# SensWear_DaughterBoard.net
KiCad netlist of a schematic drawn in Altium Designer
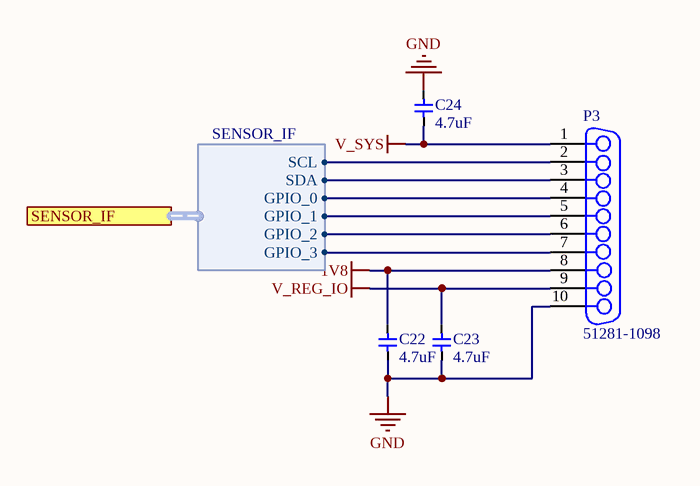
[diagram p0: SensWear_DaughterBoard.SchDoc]

(export (version "E")
  (design (tool "Eeschema 10.0.6"))
  (components
    (comp (ref "C22")
      (value "4.7uF")
      (footprint "CAPC1005X05N")
      (description "Multilayer Ceramic Capacitor, 4.7 uF, 10 V, ± 20%, X5R, 0402 [1005 Metric]")
      (fields
        (field (name "MANUFACTURER") "Murata")
        (field (name "MANUFACTURER PART NUMBER") "GRM155R61A475MEAAD")
      )
      (libsource (lib "OpenRingComponents") (part "GRM155R61A475MEAAD"))
    )
    (comp (ref "C23")
      (value "4.7uF")
      (footprint "CAPC1005X05N")
      (description "Multilayer Ceramic Capacitor, 4.7 uF, 10 V, ± 20%, X5R, 0402 [1005 Metric]")
      (fields
        (field (name "MANUFACTURER") "Murata")
        (field (name "MANUFACTURER PART NUMBER") "GRM155R61A475MEAAD")
      )
      (libsource (lib "OpenRingComponents") (part "GRM155R61A475MEAAD"))
    )
    (comp (ref "C24")
      (value "4.7uF")
      (footprint "CAPC1005X05N")
      (description "Multilayer Ceramic Capacitor, 4.7 uF, 10 V, ± 20%, X5R, 0402 [1005 Metric]")
      (fields
        (field (name "MANUFACTURER") "Murata")
        (field (name "MANUFACTURER PART NUMBER") "GRM155R61A475MEAAD")
      )
      (libsource (lib "OpenRingComponents") (part "GRM155R61A475MEAAD"))
    )
    (comp (ref "P3")
      (value "51281-1098")
      (footprint "51281-1098")
      (description "FFC/FPC Connector, Surface Mount, Right-Angle, Non-ZIF, Dual Contact Style")
      (fields (field (name "MANUFACTURER") "Molex"))
      (libsource (lib "Connectors") (part "51281-1098"))
    )
  )
  (nets
    (net (code "2") (name "/GPIO_0") (class "Default")
      (node (ref "P3") (pin "4") (pinfunction "4_4") (pintype "passive"))
    )
    (net (code "3") (name "/GPIO_1") (class "Default")
      (node (ref "P3") (pin "5") (pinfunction "5_5") (pintype "passive"))
    )
    (net (code "4") (name "/GPIO_2") (class "Default")
      (node (ref "P3") (pin "6") (pinfunction "6_6") (pintype "passive"))
    )
    (net (code "5") (name "/GPIO_3") (class "Default")
      (node (ref "P3") (pin "7") (pinfunction "7_7") (pintype "passive"))
    )
    (net (code "6") (name "/SCL") (class "Default")
      (node (ref "P3") (pin "2") (pinfunction "2_2") (pintype "passive"))
    )
    (net (code "7") (name "/SDA") (class "Default")
      (node (ref "P3") (pin "3") (pinfunction "3_3") (pintype "passive"))
    )
    (net (code "9") (name "1V8") (class "Default")
      (node (ref "C22") (pin "2") (pinfunction "2_2") (pintype "passive"))
      (node (ref "P3") (pin "8") (pinfunction "8_8") (pintype "passive"))
    )
    (net (code "10") (name "GND") (class "Default")
      (node (ref "C22") (pin "1") (pinfunction "1_1") (pintype "passive"))
      (node (ref "C23") (pin "1") (pinfunction "1_1") (pintype "passive"))
      (node (ref "C24") (pin "2") (pinfunction "2_2") (pintype "passive"))
      (node (ref "P3") (pin "10") (pinfunction "10_10") (pintype "passive"))
    )
    (net (code "11") (name "V_REG_IO") (class "Default")
      (node (ref "C23") (pin "2") (pinfunction "2_2") (pintype "passive"))
      (node (ref "P3") (pin "9") (pinfunction "9_9") (pintype "passive"))
    )
    (net (code "12") (name "V_SYS") (class "Default")
      (node (ref "C24") (pin "1") (pinfunction "1_1") (pintype "passive"))
      (node (ref "P3") (pin "1") (pinfunction "1_1") (pintype "passive"))
    )
  )
)
